# untitled.net
KiCad netlist of a schematic drawn in EAGLE
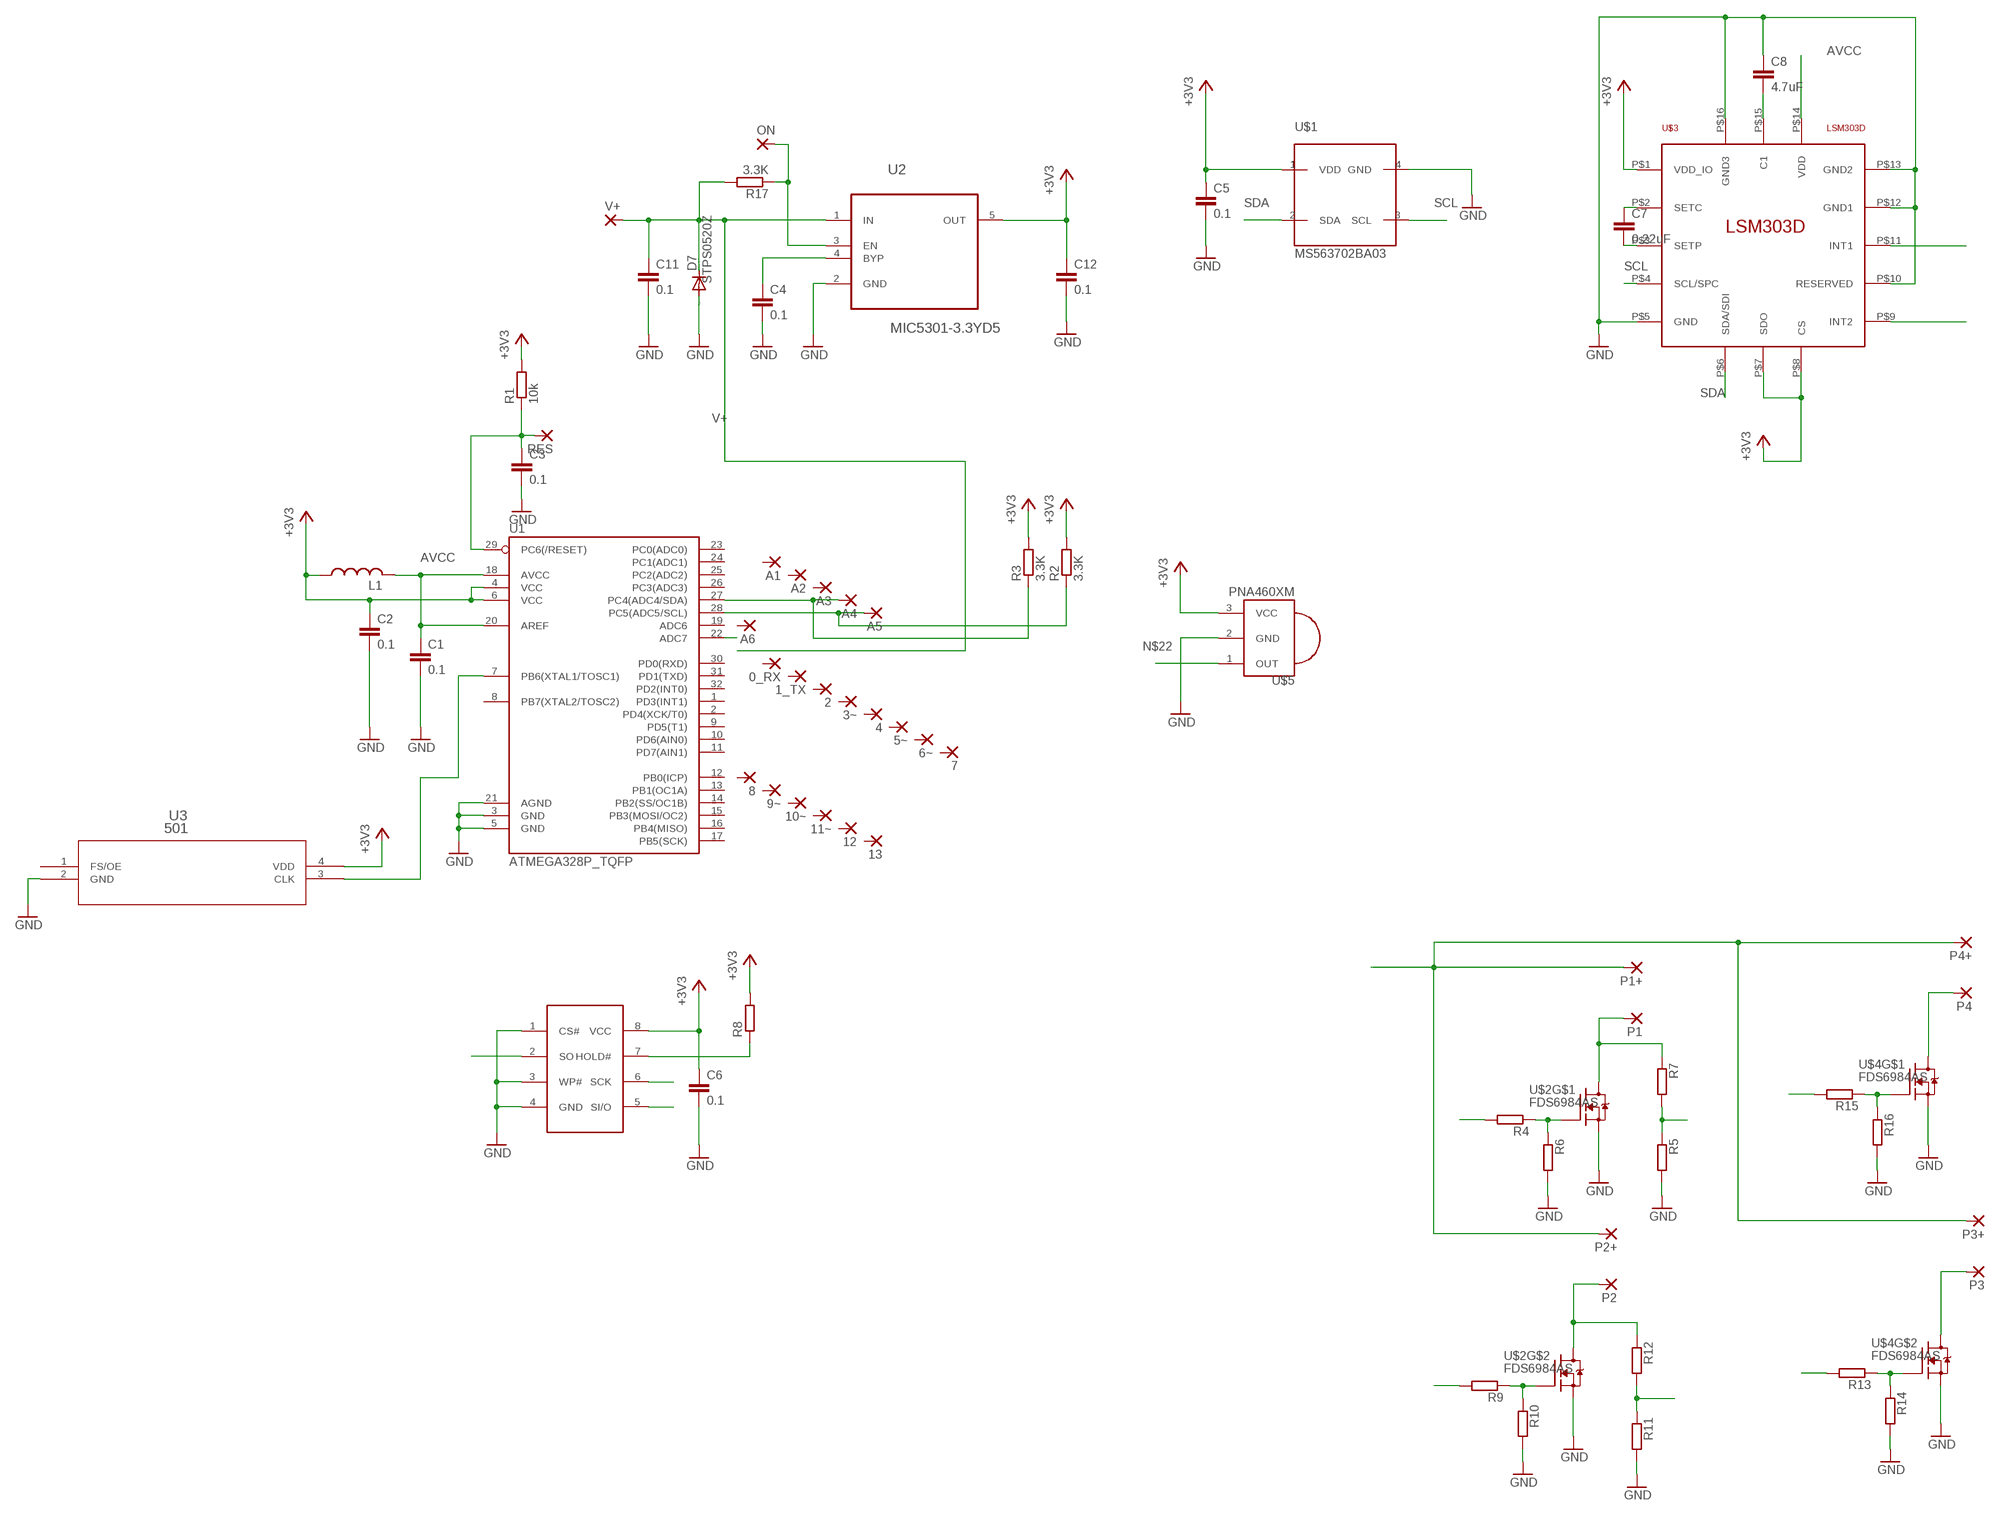
[diagram p0: schematic, sheet 1]

(export (version "E")
  (design (tool "Eeschema 10.0.6"))
  (components
    (comp (ref "0_RX")
      (value "WIREPAD1,6/0,8")
      (footprint "eagle-import:1,6_0,8")
      (libsource (lib "eagle-import") (part "WIREPAD1,6/0,8"))
    )
    (comp (ref "1_TX")
      (value "WIREPAD1,6/0,8")
      (footprint "eagle-import:1,6_0,8")
      (libsource (lib "eagle-import") (part "WIREPAD1,6/0,8"))
    )
    (comp (ref "2")
      (value "WIREPAD1,6/0,8")
      (footprint "eagle-import:1,6_0,8")
      (libsource (lib "eagle-import") (part "WIREPAD1,6/0,8"))
    )
    (comp (ref "3~")
      (value "WIREPAD1,6/0,8")
      (footprint "eagle-import:1,6_0,8")
      (libsource (lib "eagle-import") (part "WIREPAD1,6/0,8"))
    )
    (comp (ref "4")
      (value "WIREPAD1,6/0,8")
      (footprint "eagle-import:1,6_0,8")
      (libsource (lib "eagle-import") (part "WIREPAD1,6/0,8"))
    )
    (comp (ref "5~")
      (value "WIREPAD1,6/0,8")
      (footprint "eagle-import:1,6_0,8")
      (libsource (lib "eagle-import") (part "WIREPAD1,6/0,8"))
    )
    (comp (ref "6~")
      (value "WIREPAD1,6/0,8")
      (footprint "eagle-import:1,6_0,8")
      (libsource (lib "eagle-import") (part "WIREPAD1,6/0,8"))
    )
    (comp (ref "7")
      (value "WIREPAD1,6/0,8")
      (footprint "eagle-import:1,6_0,8")
      (libsource (lib "eagle-import") (part "WIREPAD1,6/0,8"))
    )
    (comp (ref "8")
      (value "WIREPAD1,6/0,8")
      (footprint "eagle-import:1,6_0,8")
      (libsource (lib "eagle-import") (part "WIREPAD1,6/0,8"))
    )
    (comp (ref "9~")
      (value "WIREPAD1,6/0,8")
      (footprint "eagle-import:1,6_0,8")
      (libsource (lib "eagle-import") (part "WIREPAD1,6/0,8"))
    )
    (comp (ref "10~")
      (value "WIREPAD1,6/0,8")
      (footprint "eagle-import:1,6_0,8")
      (libsource (lib "eagle-import") (part "WIREPAD1,6/0,8"))
    )
    (comp (ref "11~")
      (value "WIREPAD1,6/0,8")
      (footprint "eagle-import:1,6_0,8")
      (libsource (lib "eagle-import") (part "WIREPAD1,6/0,8"))
    )
    (comp (ref "12")
      (value "WIREPAD1,6/0,8")
      (footprint "eagle-import:1,6_0,8")
      (libsource (lib "eagle-import") (part "WIREPAD1,6/0,8"))
    )
    (comp (ref "13")
      (value "WIREPAD1,6/0,8")
      (footprint "eagle-import:1,6_0,8")
      (libsource (lib "eagle-import") (part "WIREPAD1,6/0,8"))
    )
    (comp (ref "A1")
      (value "WIREPAD1,6/0,8")
      (footprint "eagle-import:1,6_0,8")
      (libsource (lib "eagle-import") (part "WIREPAD1,6/0,8"))
    )
    (comp (ref "A2")
      (value "WIREPAD1,6/0,8")
      (footprint "eagle-import:1,6_0,8")
      (libsource (lib "eagle-import") (part "WIREPAD1,6/0,8"))
    )
    (comp (ref "A3")
      (value "WIREPAD1,6/0,8")
      (footprint "eagle-import:1,6_0,8")
      (libsource (lib "eagle-import") (part "WIREPAD1,6/0,8"))
    )
    (comp (ref "A4")
      (value "WIREPAD1,6/0,8")
      (footprint "eagle-import:1,6_0,8")
      (libsource (lib "eagle-import") (part "WIREPAD1,6/0,8"))
    )
    (comp (ref "A5")
      (value "WIREPAD1,6/0,8")
      (footprint "eagle-import:1,6_0,8")
      (libsource (lib "eagle-import") (part "WIREPAD1,6/0,8"))
    )
    (comp (ref "A6")
      (value "WIREPAD1,6/0,8")
      (footprint "eagle-import:1,6_0,8")
      (libsource (lib "eagle-import") (part "WIREPAD1,6/0,8"))
    )
    (comp (ref "C1")
      (value "0.1")
      (footprint "eagle-import:C0805")
      (libsource (lib "eagle-import") (part "resistor_C-EUC0805"))
    )
    (comp (ref "C2")
      (value "0.1")
      (footprint "eagle-import:C0805")
      (libsource (lib "eagle-import") (part "resistor_C-EUC0805"))
    )
    (comp (ref "C3")
      (value "0.1")
      (footprint "eagle-import:C0805")
      (libsource (lib "eagle-import") (part "resistor_C-EUC0805"))
    )
    (comp (ref "C4")
      (value "0.1")
      (footprint "eagle-import:C0805")
      (libsource (lib "eagle-import") (part "resistor_C-EUC0805"))
    )
    (comp (ref "C5")
      (value "0.1")
      (footprint "eagle-import:C0805")
      (libsource (lib "eagle-import") (part "resistor_C-EUC0805"))
    )
    (comp (ref "C6")
      (value "0.1")
      (footprint "eagle-import:C0805")
      (libsource (lib "eagle-import") (part "resistor_C-EUC0805"))
    )
    (comp (ref "C7")
      (value "0.22uF")
      (footprint "eagle-import:C0603")
      (libsource (lib "eagle-import") (part "C-EUC0603"))
    )
    (comp (ref "C8")
      (value "4.7uF")
      (footprint "eagle-import:C0603")
      (libsource (lib "eagle-import") (part "C-EUC0603"))
    )
    (comp (ref "C11")
      (value "0.1")
      (footprint "eagle-import:C0805")
      (libsource (lib "eagle-import") (part "resistor_C-EUC0805"))
    )
    (comp (ref "C12")
      (value "0.1")
      (footprint "eagle-import:C0805")
      (libsource (lib "eagle-import") (part "resistor_C-EUC0805"))
    )
    (comp (ref "D7")
      (value "CGRM4001-G")
      (footprint "eagle-import:SOD-123_MINI-SMA")
      (fields (field (name "MFGNAME") "STPS0520Z"))
      (libsource (lib "eagle-import") (part "CGRM400-G1"))
    )
    (comp (ref "L1")
      (value "L-USL2012C")
      (footprint "eagle-import:L2012C")
      (libsource (lib "eagle-import") (part "L-USL2012C"))
    )
    (comp (ref "ON")
      (value "WIREPAD1,6/0,8")
      (footprint "eagle-import:1,6_0,8")
      (libsource (lib "eagle-import") (part "WIREPAD1,6/0,8"))
    )
    (comp (ref "P1")
      (value "WIREPAD1,6/0,8")
      (footprint "eagle-import:1,6_0,8")
      (libsource (lib "eagle-import") (part "WIREPAD1,6/0,8"))
    )
    (comp (ref "P1+")
      (value "WIREPAD1,6/0,8")
      (footprint "eagle-import:1,6_0,8")
      (libsource (lib "eagle-import") (part "WIREPAD1,6/0,8"))
    )
    (comp (ref "P2")
      (value "WIREPAD1,6/0,8")
      (footprint "eagle-import:1,6_0,8")
      (libsource (lib "eagle-import") (part "WIREPAD1,6/0,8"))
    )
    (comp (ref "P2+")
      (value "WIREPAD1,6/0,8")
      (footprint "eagle-import:1,6_0,8")
      (libsource (lib "eagle-import") (part "WIREPAD1,6/0,8"))
    )
    (comp (ref "P3")
      (value "WIREPAD1,6/0,8")
      (footprint "eagle-import:1,6_0,8")
      (libsource (lib "eagle-import") (part "WIREPAD1,6/0,8"))
    )
    (comp (ref "P3+")
      (value "WIREPAD1,6/0,8")
      (footprint "eagle-import:1,6_0,8")
      (libsource (lib "eagle-import") (part "WIREPAD1,6/0,8"))
    )
    (comp (ref "P4")
      (value "WIREPAD1,6/0,8")
      (footprint "eagle-import:1,6_0,8")
      (libsource (lib "eagle-import") (part "WIREPAD1,6/0,8"))
    )
    (comp (ref "P4+")
      (value "WIREPAD1,6/0,8")
      (footprint "eagle-import:1,6_0,8")
      (libsource (lib "eagle-import") (part "WIREPAD1,6/0,8"))
    )
    (comp (ref "R1")
      (value "10k")
      (footprint "eagle-import:R0805")
      (libsource (lib "eagle-import") (part "R-EU_R0805"))
    )
    (comp (ref "R2")
      (value "3.3K")
      (footprint "eagle-import:R0805")
      (libsource (lib "eagle-import") (part "R-EU_R0805"))
    )
    (comp (ref "R3")
      (value "3.3K")
      (footprint "eagle-import:R0805")
      (libsource (lib "eagle-import") (part "R-EU_R0805"))
    )
    (comp (ref "R4")
      (value "R-EU_R0805")
      (footprint "eagle-import:R0805")
      (libsource (lib "eagle-import") (part "R-EU_R0805"))
    )
    (comp (ref "R5")
      (value "R-EU_R0805")
      (footprint "eagle-import:R0805")
      (libsource (lib "eagle-import") (part "R-EU_R0805"))
    )
    (comp (ref "R6")
      (value "R-EU_R0805")
      (footprint "eagle-import:R0805")
      (libsource (lib "eagle-import") (part "R-EU_R0805"))
    )
    (comp (ref "R7")
      (value "R-EU_R0805")
      (footprint "eagle-import:R0805")
      (libsource (lib "eagle-import") (part "R-EU_R0805"))
    )
    (comp (ref "R8")
      (value "R-EU_R0805")
      (footprint "eagle-import:R0805")
      (libsource (lib "eagle-import") (part "R-EU_R0805"))
    )
    (comp (ref "R9")
      (value "R-EU_R0805")
      (footprint "eagle-import:R0805")
      (libsource (lib "eagle-import") (part "R-EU_R0805"))
    )
    (comp (ref "R10")
      (value "R-EU_R0805")
      (footprint "eagle-import:R0805")
      (libsource (lib "eagle-import") (part "R-EU_R0805"))
    )
    (comp (ref "R11")
      (value "R-EU_R0805")
      (footprint "eagle-import:R0805")
      (libsource (lib "eagle-import") (part "R-EU_R0805"))
    )
    (comp (ref "R12")
      (value "R-EU_R0805")
      (footprint "eagle-import:R0805")
      (libsource (lib "eagle-import") (part "R-EU_R0805"))
    )
    (comp (ref "R13")
      (value "R-EU_R0805")
      (footprint "eagle-import:R0805")
      (libsource (lib "eagle-import") (part "R-EU_R0805"))
    )
    (comp (ref "R14")
      (value "R-EU_R0805")
      (footprint "eagle-import:R0805")
      (libsource (lib "eagle-import") (part "R-EU_R0805"))
    )
    (comp (ref "R15")
      (value "R-EU_R0805")
      (footprint "eagle-import:R0805")
      (libsource (lib "eagle-import") (part "R-EU_R0805"))
    )
    (comp (ref "R16")
      (value "R-EU_R0805")
      (footprint "eagle-import:R0805")
      (libsource (lib "eagle-import") (part "R-EU_R0805"))
    )
    (comp (ref "R17")
      (value "3.3K")
      (footprint "eagle-import:R0805")
      (libsource (lib "eagle-import") (part "R-EU_R0805"))
    )
    (comp (ref "RES")
      (value "WIREPAD1,6/0,8")
      (footprint "eagle-import:1,6_0,8")
      (libsource (lib "eagle-import") (part "WIREPAD1,6/0,8"))
    )
    (comp (ref "U$1")
      (value "MS563702BA03")
      (footprint "eagle-import:MS5637")
      (libsource (lib "eagle-import") (part "MS563702BA03"))
    )
    (comp (ref "U$2")
      (value "FDS6984AS")
      (footprint "eagle-import:SO8")
      (fields
        (field (name "FARNELL") "2454158")
        (field (name "MFG") "FDS6984AS")
        (field (name "URL") "http://lv.farnell.com/fairchild-semiconductor/fds6984as/mosfet-dual-n-ch-30v-8-5a-soic/dp/2454158")
      )
      (libsource (lib "eagle-import") (part "FDS6984AS"))
    )
    (comp (ref "U$3")
      (value "LSM303D")
      (footprint "eagle-import:TFLGA16L")
      (libsource (lib "eagle-import") (part "LSM303D"))
    )
    (comp (ref "U$4")
      (value "FDS6984AS")
      (footprint "eagle-import:SO8")
      (fields
        (field (name "FARNELL") "2454158")
        (field (name "MFG") "FDS6984AS")
        (field (name "URL") "http://lv.farnell.com/fairchild-semiconductor/fds6984as/mosfet-dual-n-ch-30v-8-5a-soic/dp/2454158")
      )
      (libsource (lib "eagle-import") (part "FDS6984AS"))
    )
    (comp (ref "U$5")
      (value "PNA460XM")
      (footprint "eagle-import:PNA460XM")
      (libsource (lib "eagle-import") (part "PNA460XM"))
    )
    (comp (ref "U$6")
      (value "25FL208K0RMFI041")
      (footprint "eagle-import:SO08")
      (libsource (lib "eagle-import") (part "25FL208K0RMFI041"))
    )
    (comp (ref "U1")
      (value "ATMEGA328P_TQFP")
      (footprint "eagle-import:TQFP32-08")
      (libsource (lib "eagle-import") (part "ATMEGA328P_TQFP"))
    )
    (comp (ref "U2")
      (value "MIC5301-3.3YD5")
      (footprint "eagle-import:SOT95P280X130-5N")
      (fields
        (field (name "MPN") "MIC5205-3.3YM5TR")
        (field (name "MPN_1") "MIC5301-3.3YD5")
        (field (name "OC_FARNELL") "2431779")
      )
      (libsource (lib "eagle-import") (part "MIC5205-3.3YM5TR"))
    )
    (comp (ref "U3")
      (value "501")
      (footprint "eagle-import:SI501_4_2X2.5")
      (libsource (lib "eagle-import") (part "501"))
    )
    (comp (ref "V+")
      (value "WIREPAD1,6/0,8")
      (footprint "eagle-import:1,6_0,8")
      (libsource (lib "eagle-import") (part "WIREPAD1,6/0,8"))
    )
  )
  (nets
    (net (code "1") (name "+3V3") (class "Default")
      (node (ref "C12") (pin "1") (pinfunction "1_1") (pintype "passive"))
      (node (ref "C2") (pin "1") (pinfunction "1_1") (pintype "passive"))
      (node (ref "C5") (pin "1") (pinfunction "1_1") (pintype "passive"))
      (node (ref "C6") (pin "1") (pinfunction "1_1") (pintype "passive"))
      (node (ref "L1") (pin "1") (pinfunction "1_1") (pintype "passive"))
      (node (ref "R1") (pin "2") (pinfunction "2_2") (pintype "passive"))
      (node (ref "R2") (pin "2") (pinfunction "2_2") (pintype "passive"))
      (node (ref "R3") (pin "2") (pinfunction "2_2") (pintype "passive"))
      (node (ref "R8") (pin "2") (pinfunction "2_2") (pintype "passive"))
      (node (ref "U$1") (pin "1") (pinfunction "VDD_1") (pintype "bidirectional"))
      (node (ref "U$3") (pin "P$1") (pinfunction "VDD_IO_P$1") (pintype "power_in"))
      (node (ref "U$3") (pin "P$7") (pinfunction "SDO_P$7") (pintype "bidirectional"))
      (node (ref "U$3") (pin "P$8") (pinfunction "CS_P$8") (pintype "bidirectional"))
      (node (ref "U$5") (pin "3") (pinfunction "VCC_3") (pintype "power_in"))
      (node (ref "U$6") (pin "8") (pinfunction "VCC_8") (pintype "power_in"))
      (node (ref "U1") (pin "4") (pinfunction "VCC_4") (pintype "bidirectional"))
      (node (ref "U1") (pin "6") (pinfunction "VCC_6") (pintype "bidirectional"))
      (node (ref "U2") (pin "5") (pinfunction "OUT_5") (pintype "output"))
      (node (ref "U3") (pin "4") (pinfunction "VDD_4") (pintype "power_in"))
    )
    (net (code "2") (name "/AVCC") (class "Default")
      (node (ref "C1") (pin "1") (pinfunction "1_1") (pintype "passive"))
      (node (ref "L1") (pin "2") (pinfunction "2_2") (pintype "passive"))
      (node (ref "U$3") (pin "P$14") (pinfunction "VDD_P$14") (pintype "bidirectional"))
      (node (ref "U1") (pin "18") (pinfunction "AVCC_18") (pintype "bidirectional"))
      (node (ref "U1") (pin "20") (pinfunction "AREF_20") (pintype "bidirectional"))
    )
    (net (code "3") (name "/N$22") (class "Default")
      (node (ref "U$5") (pin "1") (pinfunction "OUT_1") (pintype "output"))
    )
    (net (code "4") (name "/SCL") (class "Default")
      (node (ref "A5") (pin "1") (pinfunction "P_1") (pintype "passive"))
      (node (ref "R2") (pin "1") (pinfunction "1_1") (pintype "passive"))
      (node (ref "U$1") (pin "3") (pinfunction "SCL_3") (pintype "bidirectional"))
      (node (ref "U$3") (pin "P$4") (pinfunction "SCL/SPC_P$4") (pintype "bidirectional"))
      (node (ref "U1") (pin "28") (pinfunction "PC5(ADC5/SCL)_28") (pintype "bidirectional"))
    )
    (net (code "5") (name "/SDA") (class "Default")
      (node (ref "A4") (pin "1") (pinfunction "P_1") (pintype "passive"))
      (node (ref "R3") (pin "1") (pinfunction "1_1") (pintype "passive"))
      (node (ref "U$1") (pin "2") (pinfunction "SDA_2") (pintype "bidirectional"))
      (node (ref "U$3") (pin "P$6") (pinfunction "SDA/SDI_P$6") (pintype "bidirectional"))
      (node (ref "U1") (pin "27") (pinfunction "PC4(ADC4/SDA)_27") (pintype "bidirectional"))
    )
    (net (code "6") (name "/V+") (class "Default")
      (node (ref "C11") (pin "1") (pinfunction "1_1") (pintype "passive"))
      (node (ref "D7") (pin "C") (pinfunction "C_C") (pintype "passive"))
      (node (ref "R17") (pin "2") (pinfunction "2_2") (pintype "passive"))
      (node (ref "U2") (pin "1") (pinfunction "IN_1") (pintype "input"))
      (node (ref "V+") (pin "1") (pinfunction "P_1") (pintype "passive"))
    )
    (net (code "7") (name "GND") (class "Default")
      (node (ref "C1") (pin "2") (pinfunction "2_2") (pintype "passive"))
      (node (ref "C11") (pin "2") (pinfunction "2_2") (pintype "passive"))
      (node (ref "C12") (pin "2") (pinfunction "2_2") (pintype "passive"))
      (node (ref "C2") (pin "2") (pinfunction "2_2") (pintype "passive"))
      (node (ref "C3") (pin "2") (pinfunction "2_2") (pintype "passive"))
      (node (ref "C4") (pin "2") (pinfunction "2_2") (pintype "passive"))
      (node (ref "C5") (pin "2") (pinfunction "2_2") (pintype "passive"))
      (node (ref "C6") (pin "2") (pinfunction "2_2") (pintype "passive"))
      (node (ref "C8") (pin "1") (pinfunction "1_1") (pintype "passive"))
      (node (ref "D7") (pin "A") (pinfunction "A_A") (pintype "passive"))
      (node (ref "R10") (pin "2") (pinfunction "2_2") (pintype "passive"))
      (node (ref "R11") (pin "2") (pinfunction "2_2") (pintype "passive"))
      (node (ref "R14") (pin "2") (pinfunction "2_2") (pintype "passive"))
      (node (ref "R16") (pin "2") (pinfunction "2_2") (pintype "passive"))
      (node (ref "R5") (pin "2") (pinfunction "2_2") (pintype "passive"))
      (node (ref "R6") (pin "2") (pinfunction "2_2") (pintype "passive"))
      (node (ref "U$1") (pin "4") (pinfunction "GND_4") (pintype "bidirectional"))
      (node (ref "U$2") (pin "1") (pinfunction "S_1") (pintype "passive"))
      (node (ref "U$2") (pin "3") (pinfunction "S_3") (pintype "passive"))
      (node (ref "U$3") (pin "P$10") (pinfunction "RESERVED_P$10") (pintype "bidirectional"))
      (node (ref "U$3") (pin "P$12") (pinfunction "GND1_P$12") (pintype "power_in"))
      (node (ref "U$3") (pin "P$13") (pinfunction "GND2_P$13") (pintype "bidirectional"))
      (node (ref "U$3") (pin "P$16") (pinfunction "GND3_P$16") (pintype "bidirectional"))
      (node (ref "U$3") (pin "P$5") (pinfunction "GND_P$5") (pintype "power_in"))
      (node (ref "U$4") (pin "1") (pinfunction "S_1") (pintype "passive"))
      (node (ref "U$4") (pin "3") (pinfunction "S_3") (pintype "passive"))
      (node (ref "U$5") (pin "2") (pinfunction "GND_2") (pintype "power_in"))
      (node (ref "U$6") (pin "1") (pinfunction "CS#_1") (pintype "input"))
      (node (ref "U$6") (pin "3") (pinfunction "WP#_3") (pintype "input"))
      (node (ref "U$6") (pin "4") (pinfunction "GND_4") (pintype "power_in"))
      (node (ref "U1") (pin "21") (pinfunction "AGND_21") (pintype "bidirectional"))
      (node (ref "U1") (pin "3") (pinfunction "GND_3") (pintype "bidirectional"))
      (node (ref "U1") (pin "5") (pinfunction "GND_5") (pintype "bidirectional"))
      (node (ref "U2") (pin "2") (pinfunction "GND_2") (pintype "passive"))
      (node (ref "U3") (pin "2") (pinfunction "GND_2") (pintype "power_in"))
    )
    (net (code "8") (name "Net-(ON-P)") (class "Default")
      (node (ref "ON") (pin "1") (pinfunction "P_1") (pintype "passive"))
      (node (ref "R17") (pin "1") (pinfunction "1_1") (pintype "passive"))
      (node (ref "U2") (pin "3") (pinfunction "EN_3") (pintype "input"))
    )
    (net (code "9") (name "Net-(P1+-P)") (class "Default")
      (node (ref "P1+") (pin "1") (pinfunction "P_1") (pintype "passive"))
      (node (ref "P2+") (pin "1") (pinfunction "P_1") (pintype "passive"))
      (node (ref "P3+") (pin "1") (pinfunction "P_1") (pintype "passive"))
      (node (ref "P4+") (pin "1") (pinfunction "P_1") (pintype "passive"))
    )
    (net (code "10") (name "Net-(P1-P)") (class "Default")
      (node (ref "P1") (pin "1") (pinfunction "P_1") (pintype "passive"))
      (node (ref "R7") (pin "1") (pinfunction "1_1") (pintype "passive"))
      (node (ref "U$2") (pin "5") (pinfunction "D_5") (pintype "passive"))
      (node (ref "U$2") (pin "6") (pinfunction "D_6") (pintype "passive"))
    )
    (net (code "11") (name "Net-(P2-P)") (class "Default")
      (node (ref "P2") (pin "1") (pinfunction "P_1") (pintype "passive"))
      (node (ref "R12") (pin "1") (pinfunction "1_1") (pintype "passive"))
      (node (ref "U$2") (pin "7") (pinfunction "D_7") (pintype "passive"))
      (node (ref "U$2") (pin "8") (pinfunction "D_8") (pintype "passive"))
    )
    (net (code "12") (name "Net-(P3-P)") (class "Default")
      (node (ref "P3") (pin "1") (pinfunction "P_1") (pintype "passive"))
      (node (ref "U$4") (pin "7") (pinfunction "D_7") (pintype "passive"))
      (node (ref "U$4") (pin "8") (pinfunction "D_8") (pintype "passive"))
    )
    (net (code "13") (name "Net-(P4-P)") (class "Default")
      (node (ref "P4") (pin "1") (pinfunction "P_1") (pintype "passive"))
      (node (ref "U$4") (pin "5") (pinfunction "D_5") (pintype "passive"))
      (node (ref "U$4") (pin "6") (pinfunction "D_6") (pintype "passive"))
    )
    (net (code "14") (name "Net-(R5-Pad1)") (class "Default")
      (node (ref "R5") (pin "1") (pinfunction "1_1") (pintype "passive"))
      (node (ref "R7") (pin "2") (pinfunction "2_2") (pintype "passive"))
    )
    (net (code "15") (name "Net-(R11-Pad1)") (class "Default")
      (node (ref "R11") (pin "1") (pinfunction "1_1") (pintype "passive"))
      (node (ref "R12") (pin "2") (pinfunction "2_2") (pintype "passive"))
    )
    (net (code "16") (name "Net-(RES-P)") (class "Default")
      (node (ref "C3") (pin "1") (pinfunction "1_1") (pintype "passive"))
      (node (ref "R1") (pin "1") (pinfunction "1_1") (pintype "passive"))
      (node (ref "RES") (pin "1") (pinfunction "P_1") (pintype "passive"))
      (node (ref "U1") (pin "29") (pinfunction "PC6(/RESET)_29") (pintype "bidirectional"))
    )
    (net (code "17") (name "Net-(U$2A-G)") (class "Default")
      (node (ref "R4") (pin "1") (pinfunction "1_1") (pintype "passive"))
      (node (ref "R6") (pin "1") (pinfunction "1_1") (pintype "passive"))
      (node (ref "U$2") (pin "4") (pinfunction "G_4") (pintype "passive"))
    )
    (net (code "18") (name "Net-(U$2B-G)") (class "Default")
      (node (ref "R10") (pin "1") (pinfunction "1_1") (pintype "passive"))
      (node (ref "R9") (pin "1") (pinfunction "1_1") (pintype "passive"))
      (node (ref "U$2") (pin "2") (pinfunction "G_2") (pintype "passive"))
    )
    (net (code "19") (name "Net-(U$3-C1)") (class "Default")
      (node (ref "C8") (pin "2") (pinfunction "2_2") (pintype "passive"))
      (node (ref "U$3") (pin "P$15") (pinfunction "C1_P$15") (pintype "bidirectional"))
    )
    (net (code "20") (name "Net-(U$3-SETC)") (class "Default")
      (node (ref "C7") (pin "1") (pinfunction "1_1") (pintype "passive"))
      (node (ref "U$3") (pin "P$2") (pinfunction "SETC_P$2") (pintype "bidirectional"))
    )
    (net (code "21") (name "Net-(U$3-SETP)") (class "Default")
      (node (ref "C7") (pin "2") (pinfunction "2_2") (pintype "passive"))
      (node (ref "U$3") (pin "P$3") (pinfunction "SETP_P$3") (pintype "bidirectional"))
    )
    (net (code "22") (name "Net-(U$4A-G)") (class "Default")
      (node (ref "R15") (pin "1") (pinfunction "1_1") (pintype "passive"))
      (node (ref "R16") (pin "1") (pinfunction "1_1") (pintype "passive"))
      (node (ref "U$4") (pin "4") (pinfunction "G_4") (pintype "passive"))
    )
    (net (code "23") (name "Net-(U$4B-G)") (class "Default")
      (node (ref "R13") (pin "1") (pinfunction "1_1") (pintype "passive"))
      (node (ref "R14") (pin "1") (pinfunction "1_1") (pintype "passive"))
      (node (ref "U$4") (pin "2") (pinfunction "G_2") (pintype "passive"))
    )
    (net (code "24") (name "Net-(U$6-HOLD#)") (class "Default")
      (node (ref "R8") (pin "1") (pinfunction "1_1") (pintype "passive"))
      (node (ref "U$6") (pin "7") (pinfunction "HOLD#_7") (pintype "input"))
    )
    (net (code "25") (name "Net-(U1-PB6(XTAL1{slash}TOSC1))") (class "Default")
      (node (ref "U1") (pin "7") (pinfunction "PB6(XTAL1/TOSC1)_7") (pintype "bidirectional"))
      (node (ref "U3") (pin "3") (pinfunction "CLK_3") (pintype "output"))
    )
    (net (code "26") (name "Net-(U2-BYP)") (class "Default")
      (node (ref "C4") (pin "1") (pinfunction "1_1") (pintype "passive"))
      (node (ref "U2") (pin "4") (pinfunction "BYP_4") (pintype "input"))
    )
    (net (code "27") (name "unconnected-(0_RX-P-Pad1)") (class "Default")
      (node (ref "0_RX") (pin "1") (pinfunction "P_1") (pintype "passive"))
    )
    (net (code "28") (name "unconnected-(1_TX-P-Pad1)") (class "Default")
      (node (ref "1_TX") (pin "1") (pinfunction "P_1") (pintype "passive"))
    )
    (net (code "29") (name "unconnected-(2-P-Pad1)") (class "Default")
      (node (ref "2") (pin "1") (pinfunction "P_1") (pintype "passive"))
    )
    (net (code "30") (name "unconnected-(3~-P-Pad1)") (class "Default")
      (node (ref "3~") (pin "1") (pinfunction "P_1") (pintype "passive"))
    )
    (net (code "31") (name "unconnected-(4-P-Pad1)") (class "Default")
      (node (ref "4") (pin "1") (pinfunction "P_1") (pintype "passive"))
    )
    (net (code "32") (name "unconnected-(5~-P-Pad1)") (class "Default")
      (node (ref "5~") (pin "1") (pinfunction "P_1") (pintype "passive"))
    )
    (net (code "33") (name "unconnected-(6~-P-Pad1)") (class "Default")
      (node (ref "6~") (pin "1") (pinfunction "P_1") (pintype "passive"))
    )
    (net (code "34") (name "unconnected-(7-P-Pad1)") (class "Default")
      (node (ref "7") (pin "1") (pinfunction "P_1") (pintype "passive"))
    )
    (net (code "35") (name "unconnected-(8-P-Pad1)") (class "Default")
      (node (ref "8") (pin "1") (pinfunction "P_1") (pintype "passive"))
    )
    (net (code "36") (name "unconnected-(9~-P-Pad1)") (class "Default")
      (node (ref "9~") (pin "1") (pinfunction "P_1") (pintype "passive"))
    )
    (net (code "37") (name "unconnected-(10~-P-Pad1)") (class "Default")
      (node (ref "10~") (pin "1") (pinfunction "P_1") (pintype "passive"))
    )
    (net (code "38") (name "unconnected-(11~-P-Pad1)") (class "Default")
      (node (ref "11~") (pin "1") (pinfunction "P_1") (pintype "passive"))
    )
    (net (code "39") (name "unconnected-(12-P-Pad1)") (class "Default")
      (node (ref "12") (pin "1") (pinfunction "P_1") (pintype "passive"))
    )
    (net (code "40") (name "unconnected-(13-P-Pad1)") (class "Default")
      (node (ref "13") (pin "1") (pinfunction "P_1") (pintype "passive"))
    )
    (net (code "41") (name "unconnected-(A1-P-Pad1)") (class "Default")
      (node (ref "A1") (pin "1") (pinfunction "P_1") (pintype "passive"))
    )
    (net (code "42") (name "unconnected-(A2-P-Pad1)") (class "Default")
      (node (ref "A2") (pin "1") (pinfunction "P_1") (pintype "passive"))
    )
    (net (code "43") (name "unconnected-(A3-P-Pad1)") (class "Default")
      (node (ref "A3") (pin "1") (pinfunction "P_1") (pintype "passive"))
    )
    (net (code "44") (name "unconnected-(A6-P-Pad1)") (class "Default")
      (node (ref "A6") (pin "1") (pinfunction "P_1") (pintype "passive"))
    )
    (net (code "45") (name "unconnected-(R4-Pad2)") (class "Default")
      (node (ref "R4") (pin "2") (pinfunction "2_2") (pintype "passive"))
    )
    (net (code "46") (name "unconnected-(R9-Pad2)") (class "Default")
      (node (ref "R9") (pin "2") (pinfunction "2_2") (pintype "passive"))
    )
    (net (code "47") (name "unconnected-(R13-Pad2)") (class "Default")
      (node (ref "R13") (pin "2") (pinfunction "2_2") (pintype "passive"))
    )
    (net (code "48") (name "unconnected-(R15-Pad2)") (class "Default")
      (node (ref "R15") (pin "2") (pinfunction "2_2") (pintype "passive"))
    )
    (net (code "49") (name "unconnected-(U$3-INT1-PadP$11)") (class "Default")
      (node (ref "U$3") (pin "P$11") (pinfunction "INT1_P$11") (pintype "bidirectional"))
    )
    (net (code "50") (name "unconnected-(U$3-INT2-PadP$9)") (class "Default")
      (node (ref "U$3") (pin "P$9") (pinfunction "INT2_P$9") (pintype "bidirectional"))
    )
    (net (code "51") (name "unconnected-(U$6-SCK-Pad6)") (class "Default")
      (node (ref "U$6") (pin "6") (pinfunction "SCK_6") (pintype "input"))
    )
    (net (code "52") (name "unconnected-(U$6-SI{slash}O-Pad5)") (class "Default")
      (node (ref "U$6") (pin "5") (pinfunction "SI/O_5") (pintype "bidirectional"))
    )
    (net (code "53") (name "unconnected-(U$6-SO-Pad2)") (class "Default")
      (node (ref "U$6") (pin "2") (pinfunction "SO_2") (pintype "output"))
    )
    (net (code "54") (name "unconnected-(U1-ADC6-Pad19)") (class "Default")
      (node (ref "U1") (pin "19") (pinfunction "ADC6_19") (pintype "bidirectional"))
    )
    (net (code "55") (name "unconnected-(U1-ADC7-Pad22)") (class "Default")
      (node (ref "U1") (pin "22") (pinfunction "ADC7_22") (pintype "bidirectional"))
    )
    (net (code "56") (name "unconnected-(U1-PB0(ICP)-Pad12)") (class "Default")
      (node (ref "U1") (pin "12") (pinfunction "PB0(ICP)_12") (pintype "bidirectional"))
    )
    (net (code "57") (name "unconnected-(U1-PB1(OC1A)-Pad13)") (class "Default")
      (node (ref "U1") (pin "13") (pinfunction "PB1(OC1A)_13") (pintype "bidirectional"))
    )
    (net (code "58") (name "unconnected-(U1-PB2(SS{slash}OC1B)-Pad14)") (class "Default")
      (node (ref "U1") (pin "14") (pinfunction "PB2(SS/OC1B)_14") (pintype "bidirectional"))
    )
    (net (code "59") (name "unconnected-(U1-PB3(MOSI{slash}OC2)-Pad15)") (class "Default")
      (node (ref "U1") (pin "15") (pinfunction "PB3(MOSI/OC2)_15") (pintype "bidirectional"))
    )
    (net (code "60") (name "unconnected-(U1-PB4(MISO)-Pad16)") (class "Default")
      (node (ref "U1") (pin "16") (pinfunction "PB4(MISO)_16") (pintype "bidirectional"))
    )
    (net (code "61") (name "unconnected-(U1-PB5(SCK)-Pad17)") (class "Default")
      (node (ref "U1") (pin "17") (pinfunction "PB5(SCK)_17") (pintype "bidirectional"))
    )
    (net (code "62") (name "unconnected-(U1-PB7(XTAL2{slash}TOSC2)-Pad8)") (class "Default")
      (node (ref "U1") (pin "8") (pinfunction "PB7(XTAL2/TOSC2)_8") (pintype "bidirectional"))
    )
    (net (code "63") (name "unconnected-(U1-PC0(ADC0)-Pad23)") (class "Default")
      (node (ref "U1") (pin "23") (pinfunction "PC0(ADC0)_23") (pintype "bidirectional"))
    )
    (net (code "64") (name "unconnected-(U1-PC1(ADC1)-Pad24)") (class "Default")
      (node (ref "U1") (pin "24") (pinfunction "PC1(ADC1)_24") (pintype "bidirectional"))
    )
    (net (code "65") (name "unconnected-(U1-PC2(ADC2)-Pad25)") (class "Default")
      (node (ref "U1") (pin "25") (pinfunction "PC2(ADC2)_25") (pintype "bidirectional"))
    )
    (net (code "66") (name "unconnected-(U1-PC3(ADC3)-Pad26)") (class "Default")
      (node (ref "U1") (pin "26") (pinfunction "PC3(ADC3)_26") (pintype "bidirectional"))
    )
    (net (code "67") (name "unconnected-(U1-PD0(RXD)-Pad30)") (class "Default")
      (node (ref "U1") (pin "30") (pinfunction "PD0(RXD)_30") (pintype "bidirectional"))
    )
    (net (code "68") (name "unconnected-(U1-PD1(TXD)-Pad31)") (class "Default")
      (node (ref "U1") (pin "31") (pinfunction "PD1(TXD)_31") (pintype "bidirectional"))
    )
    (net (code "69") (name "unconnected-(U1-PD2(INT0)-Pad32)") (class "Default")
      (node (ref "U1") (pin "32") (pinfunction "PD2(INT0)_32") (pintype "bidirectional"))
    )
    (net (code "70") (name "unconnected-(U1-PD3(INT1)-Pad1)") (class "Default")
      (node (ref "U1") (pin "1") (pinfunction "PD3(INT1)_1") (pintype "bidirectional"))
    )
    (net (code "71") (name "unconnected-(U1-PD4(XCK{slash}T0)-Pad2)") (class "Default")
      (node (ref "U1") (pin "2") (pinfunction "PD4(XCK/T0)_2") (pintype "bidirectional"))
    )
    (net (code "72") (name "unconnected-(U1-PD5(T1)-Pad9)") (class "Default")
      (node (ref "U1") (pin "9") (pinfunction "PD5(T1)_9") (pintype "bidirectional"))
    )
    (net (code "73") (name "unconnected-(U1-PD6(AIN0)-Pad10)") (class "Default")
      (node (ref "U1") (pin "10") (pinfunction "PD6(AIN0)_10") (pintype "bidirectional"))
    )
    (net (code "74") (name "unconnected-(U1-PD7(AIN1)-Pad11)") (class "Default")
      (node (ref "U1") (pin "11") (pinfunction "PD7(AIN1)_11") (pintype "bidirectional"))
    )
    (net (code "75") (name "unconnected-(U3-FS{slash}OE-Pad1)") (class "Default")
      (node (ref "U3") (pin "1") (pinfunction "FS/OE_1") (pintype "passive"))
    )
  )
)
